# voltage-divider.net
KiCad netlist of a schematic drawn in EAGLE
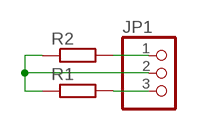
[diagram p0: schematic, sheet 1]

(export (version "E")
  (design (tool "Eeschema 10.0.6"))
  (components
    (comp (ref "JP1")
      (value "PINHD-1X3")
      (footprint "eagle-import:1X03")
      (libsource (lib "eagle-import") (part "PINHD-1X3"))
    )
    (comp (ref "R1")
      (value "R-EU_R0805")
      (footprint "eagle-import:R0805")
      (libsource (lib "eagle-import") (part "R-EU_R0805"))
    )
    (comp (ref "R2")
      (value "R-EU_R0805")
      (footprint "eagle-import:R0805")
      (libsource (lib "eagle-import") (part "R-EU_R0805"))
    )
  )
  (nets
    (net (code "1") (name "Net-(JP1-Pad1)") (class "Default")
      (node (ref "JP1") (pin "1") (pinfunction "1_1") (pintype "passive"))
      (node (ref "R2") (pin "2") (pinfunction "2_2") (pintype "passive"))
    )
    (net (code "2") (name "Net-(JP1-Pad2)") (class "Default")
      (node (ref "JP1") (pin "2") (pinfunction "2_2") (pintype "passive"))
      (node (ref "R1") (pin "1") (pinfunction "1_1") (pintype "passive"))
      (node (ref "R2") (pin "1") (pinfunction "1_1") (pintype "passive"))
    )
    (net (code "3") (name "Net-(JP1-Pad3)") (class "Default")
      (node (ref "JP1") (pin "3") (pinfunction "3_3") (pintype "passive"))
      (node (ref "R1") (pin "2") (pinfunction "2_2") (pintype "passive"))
    )
  )
)
